# PetFeeder2.net
KiCad netlist of a schematic drawn in EAGLE
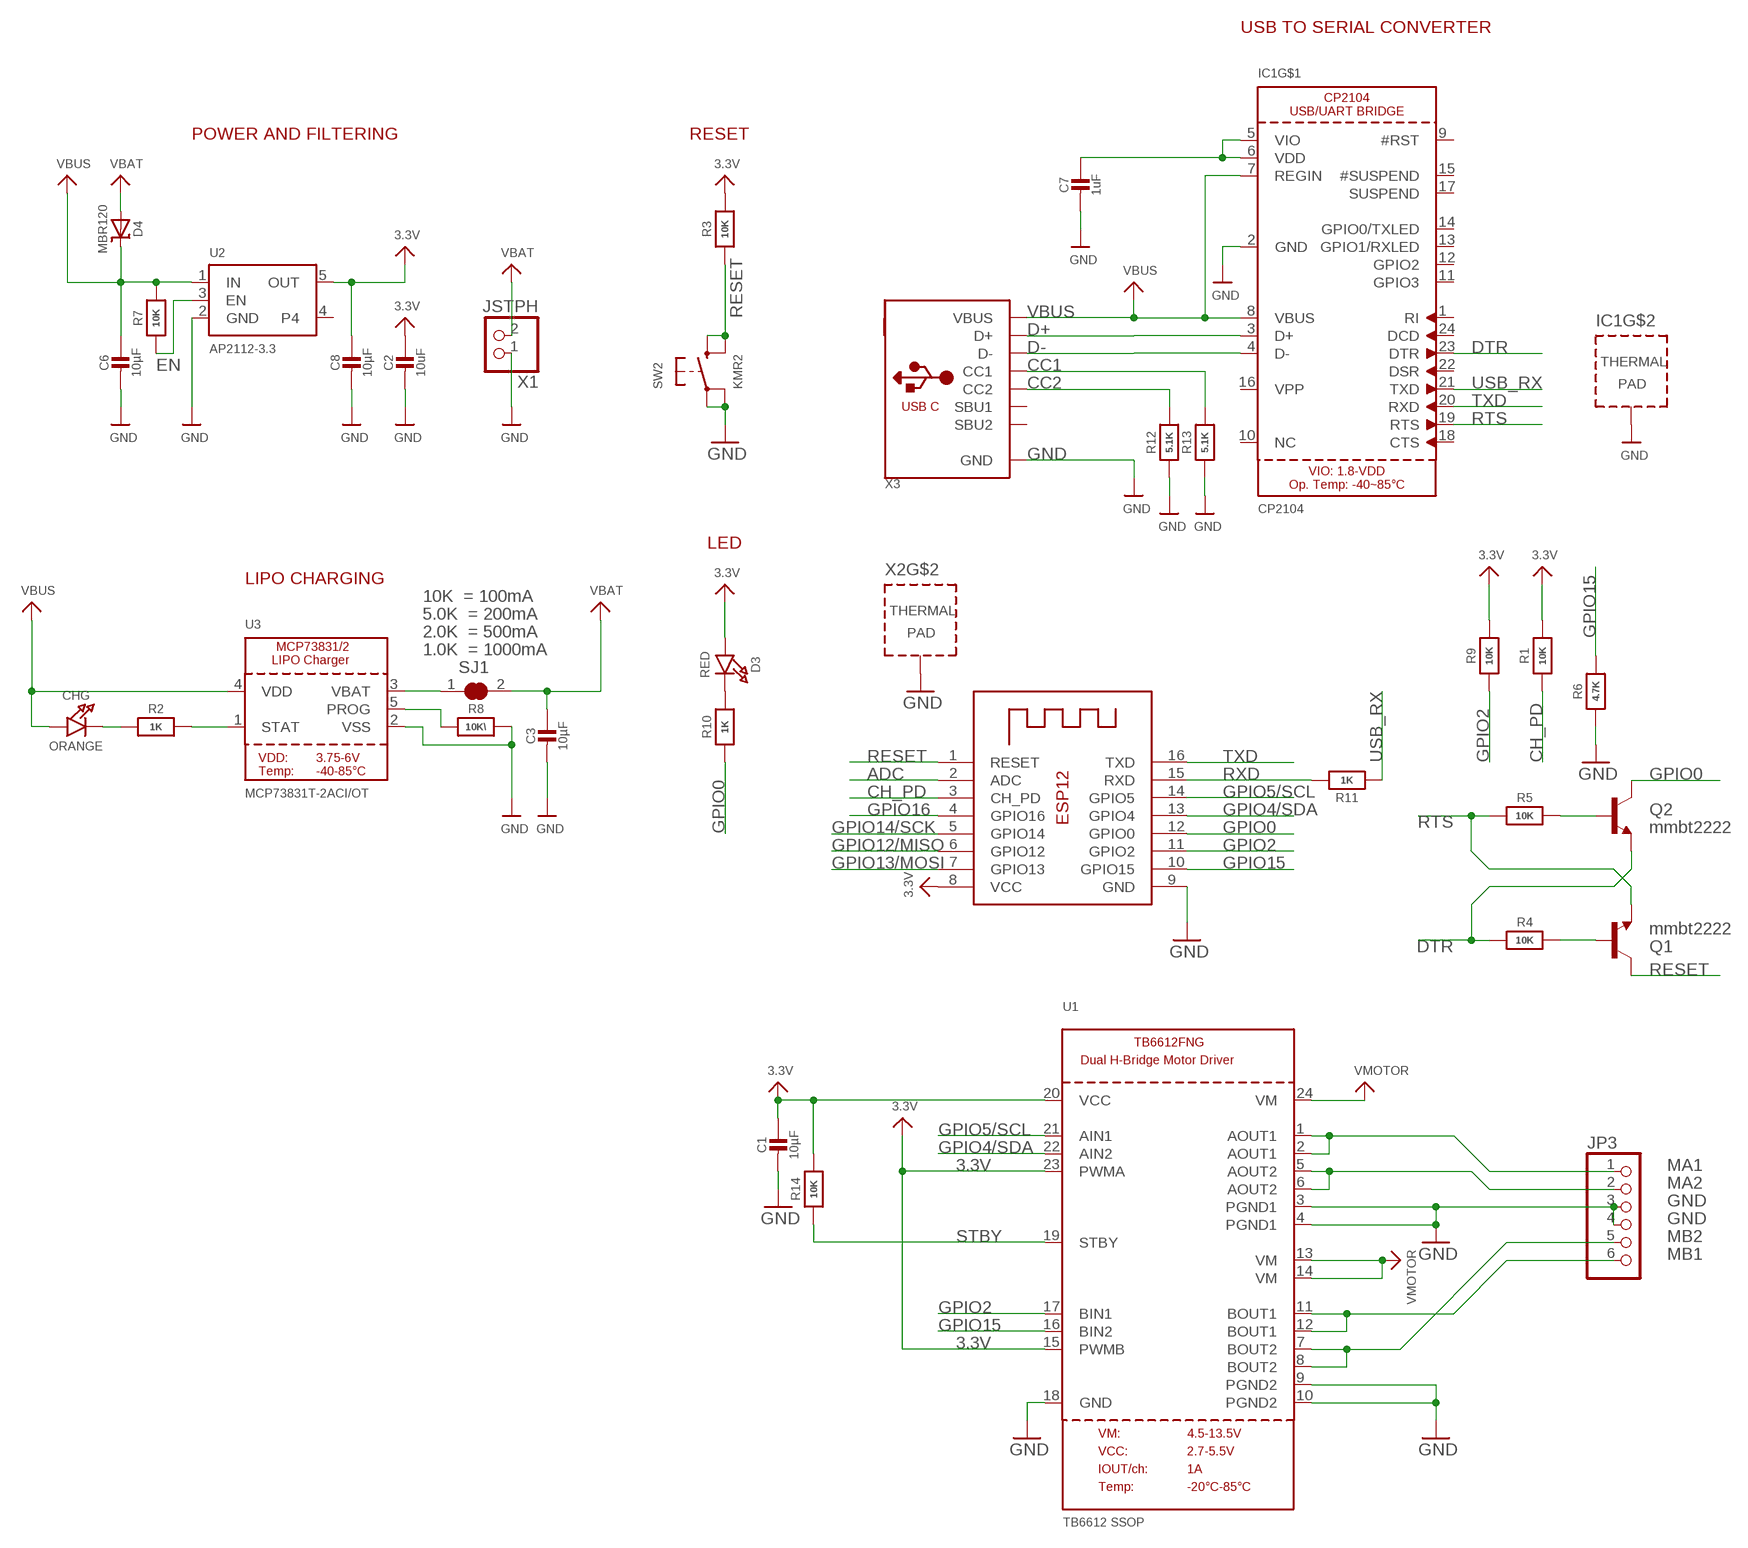
[diagram p0: schematic, sheet 1]

(export (version "E")
  (design (tool "Eeschema 10.0.6"))
  (components
    (comp (ref "C1")
      (value "10µF")
      (footprint "eagle-import:0805-NO")
      (libsource (lib "eagle-import") (part "CAP_CERAMIC0805-NOOUTLINE"))
    )
    (comp (ref "C2")
      (value "10uF")
      (footprint "eagle-import:0805-NO")
      (libsource (lib "eagle-import") (part "CAP_CERAMIC0805-NOOUTLINE"))
    )
    (comp (ref "C3")
      (value "10µF")
      (footprint "eagle-import:0805-NO")
      (libsource (lib "eagle-import") (part "CAP_CERAMIC0805-NOOUTLINE"))
    )
    (comp (ref "C6")
      (value "10µF")
      (footprint "eagle-import:0805-NO")
      (libsource (lib "eagle-import") (part "CAP_CERAMIC0805-NOOUTLINE"))
    )
    (comp (ref "C7")
      (value "1uF")
      (footprint "eagle-import:0603-NO")
      (libsource (lib "eagle-import") (part "CAP_CERAMIC0603_NO"))
    )
    (comp (ref "C8")
      (value "10µF")
      (footprint "eagle-import:0805-NO")
      (libsource (lib "eagle-import") (part "CAP_CERAMIC0805-NOOUTLINE"))
    )
    (comp (ref "CHG")
      (value "ORANGE")
      (footprint "eagle-import:CHIPLED_0805_NOOUTLINE")
      (libsource (lib "eagle-import") (part "LED0805_NOOUTLINE"))
    )
    (comp (ref "D3")
      (value "RED")
      (footprint "eagle-import:CHIPLED_0805_NOOUTLINE")
      (libsource (lib "eagle-import") (part "LED0805_NOOUTLINE"))
    )
    (comp (ref "D4")
      (value "MBR120")
      (footprint "eagle-import:SOD-123")
      (libsource (lib "eagle-import") (part "DIODE-SCHOTTKYSOD-123"))
    )
    (comp (ref "IC1")
      (value "CP2104")
      (footprint "eagle-import:QFN24_4MM_SMSC")
      (libsource (lib "eagle-import") (part "CP2104"))
    )
    (comp (ref "JP3")
      (value "PINHD-1X6CB")
      (footprint "eagle-import:1X06-CLEANBIG")
      (libsource (lib "eagle-import") (part "PINHD-1X6CB"))
    )
    (comp (ref "Q1")
      (value "mmbt2222")
      (footprint "eagle-import:SOT23-3")
      (libsource (lib "eagle-import") (part "TRANSISTOR_NPNSOT23-3"))
    )
    (comp (ref "Q2")
      (value "mmbt2222")
      (footprint "eagle-import:SOT23-3")
      (libsource (lib "eagle-import") (part "TRANSISTOR_NPNSOT23-3"))
    )
    (comp (ref "R1")
      (value "10K")
      (footprint "eagle-import:0603-NO")
      (libsource (lib "eagle-import") (part "RESISTOR_0603_NOOUT"))
    )
    (comp (ref "R2")
      (value "1K")
      (footprint "eagle-import:0603-NO")
      (libsource (lib "eagle-import") (part "RESISTOR_0603_NOOUT"))
    )
    (comp (ref "R3")
      (value "10K")
      (footprint "eagle-import:0603-NO")
      (libsource (lib "eagle-import") (part "RESISTOR_0603_NOOUT"))
    )
    (comp (ref "R4")
      (value "10K")
      (footprint "eagle-import:0603-NO")
      (libsource (lib "eagle-import") (part "RESISTOR_0603_NOOUT"))
    )
    (comp (ref "R5")
      (value "10K")
      (footprint "eagle-import:0603-NO")
      (libsource (lib "eagle-import") (part "RESISTOR_0603_NOOUT"))
    )
    (comp (ref "R6")
      (value "4.7K")
      (footprint "eagle-import:0603-NO")
      (libsource (lib "eagle-import") (part "RESISTOR_0603_NOOUT"))
    )
    (comp (ref "R7")
      (value "10K")
      (footprint "eagle-import:0603-NO")
      (libsource (lib "eagle-import") (part "RESISTOR_0603_NOOUT"))
    )
    (comp (ref "R8")
      (value "10K\\")
      (footprint "eagle-import:0603-NO")
      (libsource (lib "eagle-import") (part "RESISTOR_0603_NOOUT"))
    )
    (comp (ref "R9")
      (value "10K")
      (footprint "eagle-import:0603-NO")
      (libsource (lib "eagle-import") (part "RESISTOR_0603_NOOUT"))
    )
    (comp (ref "R10")
      (value "1K")
      (footprint "eagle-import:0603-NO")
      (libsource (lib "eagle-import") (part "RESISTOR_0603_NOOUT"))
    )
    (comp (ref "R11")
      (value "1K")
      (footprint "eagle-import:_0603MP")
      (libsource (lib "eagle-import") (part "RESISTOR_0603MP"))
    )
    (comp (ref "R12")
      (value "5.1K")
      (footprint "eagle-import:0603-NO")
      (libsource (lib "eagle-import") (part "RESISTOR_0603_NOOUT"))
    )
    (comp (ref "R13")
      (value "5.1K")
      (footprint "eagle-import:0603-NO")
      (libsource (lib "eagle-import") (part "RESISTOR_0603_NOOUT"))
    )
    (comp (ref "R14")
      (value "10K")
      (footprint "eagle-import:0805-NO")
      (libsource (lib "eagle-import") (part "RESISTOR0805_NOOUTLINE"))
    )
    (comp (ref "SJ1")
      (value "SOLDERJUMPER_CLOSED")
      (footprint "eagle-import:SOLDERJUMPER_CLOSEDWIRE")
      (libsource (lib "eagle-import") (part "SOLDERJUMPER_CLOSED"))
    )
    (comp (ref "SW2")
      (value "KMR2")
      (footprint "eagle-import:BTN_KMR2_4.6X2.8")
      (libsource (lib "eagle-import") (part "SWITCH_TACT_SMT4.6X2.8"))
    )
    (comp (ref "U1")
      (value "TB6612 SSOP")
      (footprint "eagle-import:SSOP24")
      (libsource (lib "eagle-import") (part "TB6612FNGSSOP"))
    )
    (comp (ref "U2")
      (value "AP2112-3.3")
      (footprint "eagle-import:SOT23-5")
      (libsource (lib "eagle-import") (part "VREG_SOT23-5"))
    )
    (comp (ref "U3")
      (value "MCP73831T-2ACI/OT")
      (footprint "eagle-import:SOT23-5")
      (libsource (lib "eagle-import") (part "MCP73831/2"))
    )
    (comp (ref "X1")
      (value "JSTPH")
      (footprint "eagle-import:JSTPH2")
      (libsource (lib "eagle-import") (part "CON_JST_PH_2PIN"))
    )
    (comp (ref "X2")
      (value "ESP-12")
      (footprint "eagle-import:ESP-12S")
      (libsource (lib "eagle-import") (part "ESP-12S"))
    )
    (comp (ref "X3")
      (value "USB_C")
      (footprint "eagle-import:USB_C_CUSB31-CFM2AX-01-X")
      (libsource (lib "eagle-import") (part "USB_C"))
    )
  )
  (nets
    (net (code "1") (name "/ADC") (class "Default")
      (node (ref "X2") (pin "2") (pinfunction "ADC_2") (pintype "passive"))
    )
    (net (code "2") (name "/CC1") (class "Default")
      (node (ref "R13") (pin "2") (pinfunction "2_2") (pintype "passive"))
      (node (ref "X3") (pin "A5") (pinfunction "CC1_A5") (pintype "bidirectional"))
    )
    (net (code "3") (name "/CC2") (class "Default")
      (node (ref "R12") (pin "2") (pinfunction "2_2") (pintype "passive"))
      (node (ref "X3") (pin "B5") (pinfunction "CC2_B5") (pintype "bidirectional"))
    )
    (net (code "4") (name "/CH_PD") (class "Default")
      (node (ref "R1") (pin "1") (pinfunction "1_1") (pintype "passive"))
      (node (ref "X2") (pin "3") (pinfunction "CH_PD_3") (pintype "input"))
    )
    (net (code "5") (name "/D+") (class "Default")
      (node (ref "IC1") (pin "3") (pinfunction "D+_3") (pintype "bidirectional"))
      (node (ref "X3") (pin "A6") (pinfunction "D+_A6") (pintype "bidirectional"))
      (node (ref "X3") (pin "B6") (pinfunction "D+_B6") (pintype "bidirectional"))
    )
    (net (code "6") (name "/D-") (class "Default")
      (node (ref "IC1") (pin "4") (pinfunction "D-_4") (pintype "bidirectional"))
      (node (ref "X3") (pin "A7") (pinfunction "D-_A7") (pintype "bidirectional"))
      (node (ref "X3") (pin "B7") (pinfunction "D-_B7") (pintype "bidirectional"))
    )
    (net (code "7") (name "/DTR") (class "Default")
      (node (ref "IC1") (pin "23") (pinfunction "DTR_23") (pintype "output"))
      (node (ref "Q2") (pin "2") (pinfunction "E_2") (pintype "passive"))
      (node (ref "R4") (pin "1") (pinfunction "1_1") (pintype "passive"))
    )
    (net (code "8") (name "/EN") (class "Default")
      (node (ref "R7") (pin "1") (pinfunction "1_1") (pintype "passive"))
      (node (ref "U2") (pin "3") (pinfunction "EN_3") (pintype "input"))
    )
    (net (code "9") (name "/GPIO0") (class "Default")
      (node (ref "Q2") (pin "3") (pinfunction "C_3") (pintype "passive"))
      (node (ref "R10") (pin "1") (pinfunction "1_1") (pintype "passive"))
      (node (ref "X2") (pin "12") (pinfunction "GPIO0_12") (pintype "bidirectional"))
    )
    (net (code "10") (name "/GPIO2") (class "Default")
      (node (ref "R9") (pin "1") (pinfunction "1_1") (pintype "passive"))
      (node (ref "U1") (pin "17") (pinfunction "BIN1_17") (pintype "input"))
      (node (ref "X2") (pin "11") (pinfunction "GPIO2_11") (pintype "bidirectional"))
    )
    (net (code "11") (name "/GPIO4{slash}SDA") (class "Default")
      (node (ref "U1") (pin "22") (pinfunction "AIN2_22") (pintype "input"))
      (node (ref "X2") (pin "13") (pinfunction "GPIO4_13") (pintype "bidirectional"))
    )
    (net (code "12") (name "/GPIO5{slash}SCL") (class "Default")
      (node (ref "U1") (pin "21") (pinfunction "AIN1_21") (pintype "input"))
      (node (ref "X2") (pin "14") (pinfunction "GPIO5_14") (pintype "bidirectional"))
    )
    (net (code "13") (name "/GPIO12{slash}MISO") (class "Default")
      (node (ref "X2") (pin "6") (pinfunction "GPIO12_6") (pintype "bidirectional"))
    )
    (net (code "14") (name "/GPIO13{slash}MOSI") (class "Default")
      (node (ref "X2") (pin "7") (pinfunction "GPIO13_7") (pintype "bidirectional"))
    )
    (net (code "15") (name "/GPIO14{slash}SCK") (class "Default")
      (node (ref "X2") (pin "5") (pinfunction "GPIO14_5") (pintype "bidirectional"))
    )
    (net (code "16") (name "/GPIO15") (class "Default")
      (node (ref "R6") (pin "2") (pinfunction "2_2") (pintype "passive"))
      (node (ref "U1") (pin "16") (pinfunction "BIN2_16") (pintype "input"))
      (node (ref "X2") (pin "10") (pinfunction "GPIO15_10") (pintype "bidirectional"))
    )
    (net (code "17") (name "/GPIO16") (class "Default")
      (node (ref "X2") (pin "4") (pinfunction "GPIO16_4") (pintype "bidirectional"))
    )
    (net (code "18") (name "/MA1") (class "Default")
      (node (ref "JP3") (pin "1") (pinfunction "1_1") (pintype "passive"))
      (node (ref "U1") (pin "1") (pinfunction "AOUT1_1") (pintype "output"))
      (node (ref "U1") (pin "2") (pinfunction "AOUT1_2") (pintype "output"))
    )
    (net (code "19") (name "/MA2") (class "Default")
      (node (ref "JP3") (pin "2") (pinfunction "2_2") (pintype "passive"))
      (node (ref "U1") (pin "5") (pinfunction "AOUT2_5") (pintype "output"))
      (node (ref "U1") (pin "6") (pinfunction "AOUT2_6") (pintype "output"))
    )
    (net (code "20") (name "/MB1") (class "Default")
      (node (ref "JP3") (pin "6") (pinfunction "6_6") (pintype "passive"))
      (node (ref "U1") (pin "11") (pinfunction "BOUT1_11") (pintype "output"))
      (node (ref "U1") (pin "12") (pinfunction "BOUT1_12") (pintype "output"))
    )
    (net (code "21") (name "/MB2") (class "Default")
      (node (ref "JP3") (pin "5") (pinfunction "5_5") (pintype "passive"))
      (node (ref "U1") (pin "7") (pinfunction "BOUT2_7") (pintype "output"))
      (node (ref "U1") (pin "8") (pinfunction "BOUT2_8") (pintype "output"))
    )
    (net (code "22") (name "/RESET") (class "Default")
      (node (ref "Q1") (pin "3") (pinfunction "C_3") (pintype "passive"))
      (node (ref "R3") (pin "1") (pinfunction "1_1") (pintype "passive"))
      (node (ref "SW2") (pin "B") (pinfunction "S_B") (pintype "passive"))
      (node (ref "SW2") (pin "B'") (pinfunction "S1_B'") (pintype "passive"))
      (node (ref "X2") (pin "1") (pinfunction "RESET_1") (pintype "input"))
    )
    (net (code "23") (name "/RTS") (class "Default")
      (node (ref "IC1") (pin "19") (pinfunction "RTS_19") (pintype "output"))
      (node (ref "Q1") (pin "2") (pinfunction "E_2") (pintype "passive"))
      (node (ref "R5") (pin "1") (pinfunction "1_1") (pintype "passive"))
    )
    (net (code "24") (name "/RXD") (class "Default")
      (node (ref "R11") (pin "2") (pinfunction "2_2") (pintype "passive"))
      (node (ref "X2") (pin "15") (pinfunction "RXD_15") (pintype "input"))
    )
    (net (code "25") (name "/STBY") (class "Default")
      (node (ref "R14") (pin "1") (pinfunction "1_1") (pintype "passive"))
      (node (ref "U1") (pin "19") (pinfunction "STBY_19") (pintype "input"))
    )
    (net (code "26") (name "/TXD") (class "Default")
      (node (ref "IC1") (pin "20") (pinfunction "RXD_20") (pintype "input"))
      (node (ref "X2") (pin "16") (pinfunction "TXD_16") (pintype "output"))
    )
    (net (code "27") (name "/USB_RX") (class "Default")
      (node (ref "IC1") (pin "21") (pinfunction "TXD_21") (pintype "output"))
      (node (ref "R11") (pin "1") (pinfunction "1_1") (pintype "passive"))
    )
    (net (code "28") (name "3.3V") (class "Default")
      (node (ref "C1") (pin "1") (pinfunction "1_1") (pintype "passive"))
      (node (ref "C2") (pin "1") (pinfunction "1_1") (pintype "passive"))
      (node (ref "C8") (pin "1") (pinfunction "1_1") (pintype "passive"))
      (node (ref "D3") (pin "A") (pinfunction "A_A") (pintype "passive"))
      (node (ref "R1") (pin "2") (pinfunction "2_2") (pintype "passive"))
      (node (ref "R14") (pin "2") (pinfunction "2_2") (pintype "passive"))
      (node (ref "R3") (pin "2") (pinfunction "2_2") (pintype "passive"))
      (node (ref "R9") (pin "2") (pinfunction "2_2") (pintype "passive"))
      (node (ref "U1") (pin "15") (pinfunction "PWMB_15") (pintype "input"))
      (node (ref "U1") (pin "20") (pinfunction "VCC_20") (pintype "power_in"))
      (node (ref "U1") (pin "23") (pinfunction "PWMA_23") (pintype "input"))
      (node (ref "U2") (pin "5") (pinfunction "OUT_5") (pintype "power_in"))
      (node (ref "X2") (pin "8") (pinfunction "VCC_8") (pintype "power_in"))
    )
    (net (code "29") (name "GND") (class "Default")
      (node (ref "C1") (pin "2") (pinfunction "2_2") (pintype "passive"))
      (node (ref "C2") (pin "2") (pinfunction "2_2") (pintype "passive"))
      (node (ref "C3") (pin "2") (pinfunction "2_2") (pintype "passive"))
      (node (ref "C6") (pin "2") (pinfunction "2_2") (pintype "passive"))
      (node (ref "C7") (pin "2") (pinfunction "2_2") (pintype "passive"))
      (node (ref "C8") (pin "2") (pinfunction "2_2") (pintype "passive"))
      (node (ref "IC1") (pin "2") (pinfunction "GND_2") (pintype "power_in"))
      (node (ref "IC1") (pin "THERM") (pinfunction "TP_THERM") (pintype "power_in"))
      (node (ref "JP3") (pin "3") (pinfunction "3_3") (pintype "passive"))
      (node (ref "JP3") (pin "4") (pinfunction "4_4") (pintype "passive"))
      (node (ref "R12") (pin "1") (pinfunction "1_1") (pintype "passive"))
      (node (ref "R13") (pin "1") (pinfunction "1_1") (pintype "passive"))
      (node (ref "R6") (pin "1") (pinfunction "1_1") (pintype "passive"))
      (node (ref "R8") (pin "2") (pinfunction "2_2") (pintype "passive"))
      (node (ref "SW2") (pin "A") (pinfunction "P_A") (pintype "passive"))
      (node (ref "SW2") (pin "A'") (pinfunction "P1_A'") (pintype "passive"))
      (node (ref "U1") (pin "10") (pinfunction "PGND2_10") (pintype "power_in"))
      (node (ref "U1") (pin "18") (pinfunction "GND_18") (pintype "power_in"))
      (node (ref "U1") (pin "3") (pinfunction "PGND1_3") (pintype "power_in"))
      (node (ref "U1") (pin "4") (pinfunction "PGND1_4") (pintype "power_in"))
      (node (ref "U1") (pin "9") (pinfunction "PGND2_9") (pintype "power_in"))
      (node (ref "U2") (pin "2") (pinfunction "GND_2") (pintype "power_in"))
      (node (ref "U3") (pin "2") (pinfunction "VSS_2") (pintype "power_in"))
      (node (ref "X1") (pin "1") (pinfunction "1_1") (pintype "passive"))
      (node (ref "X2") (pin "9") (pinfunction "GND_9") (pintype "power_in"))
      (node (ref "X2") (pin "P$1") (pinfunction "TP_P$1") (pintype "power_in"))
      (node (ref "X3") (pin "A1B12") (pinfunction "GND_A1B12") (pintype "power_in"))
      (node (ref "X3") (pin "B1A12") (pinfunction "GND_B1A12") (pintype "power_in"))
    )
    (net (code "30") (name "Net-(CHG-PadC)") (class "Default")
      (node (ref "CHG") (pin "C") (pinfunction "C_C") (pintype "passive"))
      (node (ref "R2") (pin "1") (pinfunction "1_1") (pintype "passive"))
    )
    (net (code "31") (name "Net-(D3-PadC)") (class "Default")
      (node (ref "D3") (pin "C") (pinfunction "C_C") (pintype "passive"))
      (node (ref "R10") (pin "2") (pinfunction "2_2") (pintype "passive"))
    )
    (net (code "32") (name "Net-(IC1A-VDD)") (class "Default")
      (node (ref "C7") (pin "1") (pinfunction "1_1") (pintype "passive"))
      (node (ref "IC1") (pin "5") (pinfunction "VIO_5") (pintype "power_in"))
      (node (ref "IC1") (pin "6") (pinfunction "VDD_6") (pintype "power_in"))
    )
    (net (code "33") (name "Net-(Q1-B)") (class "Default")
      (node (ref "Q1") (pin "1") (pinfunction "B_1") (pintype "passive"))
      (node (ref "R4") (pin "2") (pinfunction "2_2") (pintype "passive"))
    )
    (net (code "34") (name "Net-(Q2-B)") (class "Default")
      (node (ref "Q2") (pin "1") (pinfunction "B_1") (pintype "passive"))
      (node (ref "R5") (pin "2") (pinfunction "2_2") (pintype "passive"))
    )
    (net (code "35") (name "Net-(U3-PROG)") (class "Default")
      (node (ref "R8") (pin "1") (pinfunction "1_1") (pintype "passive"))
      (node (ref "U3") (pin "5") (pinfunction "PROG_5") (pintype "input"))
    )
    (net (code "36") (name "Net-(U3-STAT)") (class "Default")
      (node (ref "R2") (pin "2") (pinfunction "2_2") (pintype "passive"))
      (node (ref "U3") (pin "1") (pinfunction "STAT_1") (pintype "output"))
    )
    (net (code "37") (name "Net-(U3-VBAT)") (class "Default")
      (node (ref "SJ1") (pin "1") (pinfunction "1_1") (pintype "passive"))
      (node (ref "U3") (pin "3") (pinfunction "VBAT_3") (pintype "power_in"))
    )
    (net (code "38") (name "VBAT") (class "Default")
      (node (ref "C3") (pin "1") (pinfunction "1_1") (pintype "passive"))
      (node (ref "D4") (pin "A") (pinfunction "A_A") (pintype "passive"))
      (node (ref "SJ1") (pin "2") (pinfunction "2_2") (pintype "passive"))
      (node (ref "X1") (pin "2") (pinfunction "2_2") (pintype "passive"))
    )
    (net (code "39") (name "VBUS") (class "Default")
      (node (ref "C6") (pin "1") (pinfunction "1_1") (pintype "passive"))
      (node (ref "CHG") (pin "A") (pinfunction "A_A") (pintype "passive"))
      (node (ref "D4") (pin "C") (pinfunction "C_C") (pintype "passive"))
      (node (ref "IC1") (pin "7") (pinfunction "REGIN_7") (pintype "power_in"))
      (node (ref "IC1") (pin "8") (pinfunction "VBUS_8") (pintype "power_in"))
      (node (ref "R7") (pin "2") (pinfunction "2_2") (pintype "passive"))
      (node (ref "U2") (pin "1") (pinfunction "IN_1") (pintype "power_in"))
      (node (ref "U3") (pin "4") (pinfunction "VDD_4") (pintype "power_in"))
      (node (ref "X3") (pin "A4B9") (pinfunction "VBUS_A4B9") (pintype "power_in"))
      (node (ref "X3") (pin "B4A9") (pinfunction "VBUS_B4A9") (pintype "power_in"))
    )
    (net (code "40") (name "VMOTOR") (class "Default")
      (node (ref "U1") (pin "13") (pinfunction "VM_13") (pintype "power_in"))
      (node (ref "U1") (pin "14") (pinfunction "VM_14") (pintype "power_in"))
      (node (ref "U1") (pin "24") (pinfunction "VM_24") (pintype "power_in"))
    )
    (net (code "41") (name "unconnected-(IC1A-#RST-Pad9)") (class "Default")
      (node (ref "IC1") (pin "9") (pinfunction "#RST_9") (pintype "bidirectional"))
    )
    (net (code "42") (name "unconnected-(IC1A-#SUSPEND-Pad15)") (class "Default")
      (node (ref "IC1") (pin "15") (pinfunction "#SUSPEND_15") (pintype "output"))
    )
    (net (code "43") (name "unconnected-(IC1A-CTS-Pad18)") (class "Default")
      (node (ref "IC1") (pin "18") (pinfunction "CTS_18") (pintype "input"))
    )
    (net (code "44") (name "unconnected-(IC1A-DCD-Pad24)") (class "Default")
      (node (ref "IC1") (pin "24") (pinfunction "DCD_24") (pintype "input"))
    )
    (net (code "45") (name "unconnected-(IC1A-DSR-Pad22)") (class "Default")
      (node (ref "IC1") (pin "22") (pinfunction "DSR_22") (pintype "input"))
    )
    (net (code "46") (name "unconnected-(IC1A-GPIO0{slash}TXLED-Pad14)") (class "Default")
      (node (ref "IC1") (pin "14") (pinfunction "GPIO0/TXLED_14") (pintype "bidirectional"))
    )
    (net (code "47") (name "unconnected-(IC1A-GPIO1{slash}RXLED-Pad13)") (class "Default")
      (node (ref "IC1") (pin "13") (pinfunction "GPIO1/RXLED_13") (pintype "bidirectional"))
    )
    (net (code "48") (name "unconnected-(IC1A-GPIO2-Pad12)") (class "Default")
      (node (ref "IC1") (pin "12") (pinfunction "GPIO2_12") (pintype "bidirectional"))
    )
    (net (code "49") (name "unconnected-(IC1A-GPIO3-Pad11)") (class "Default")
      (node (ref "IC1") (pin "11") (pinfunction "GPIO3_11") (pintype "bidirectional"))
    )
    (net (code "50") (name "unconnected-(IC1A-NC-Pad10)") (class "Default")
      (node (ref "IC1") (pin "10") (pinfunction "NC_10") (pintype "no_connect"))
    )
    (net (code "51") (name "unconnected-(IC1A-RI-Pad1)") (class "Default")
      (node (ref "IC1") (pin "1") (pinfunction "RI_1") (pintype "input"))
    )
    (net (code "52") (name "unconnected-(IC1A-SUSPEND-Pad17)") (class "Default")
      (node (ref "IC1") (pin "17") (pinfunction "SUSPEND_17") (pintype "output"))
    )
    (net (code "53") (name "unconnected-(IC1A-VPP-Pad16)") (class "Default")
      (node (ref "IC1") (pin "16") (pinfunction "VPP_16") (pintype "bidirectional"))
    )
    (net (code "54") (name "unconnected-(U2-P4-Pad4)") (class "Default")
      (node (ref "U2") (pin "4") (pinfunction "P4_4") (pintype "bidirectional"))
    )
    (net (code "55") (name "unconnected-(X3-SBU1-PadA8)") (class "Default")
      (node (ref "X3") (pin "A8") (pinfunction "SBU1_A8") (pintype "bidirectional"))
    )
    (net (code "56") (name "unconnected-(X3-SBU2-PadB8)") (class "Default")
      (node (ref "X3") (pin "B8") (pinfunction "SBU2_B8") (pintype "bidirectional"))
    )
  )
)
